# Connectors.net
KiCad netlist of a schematic drawn in Altium Designer
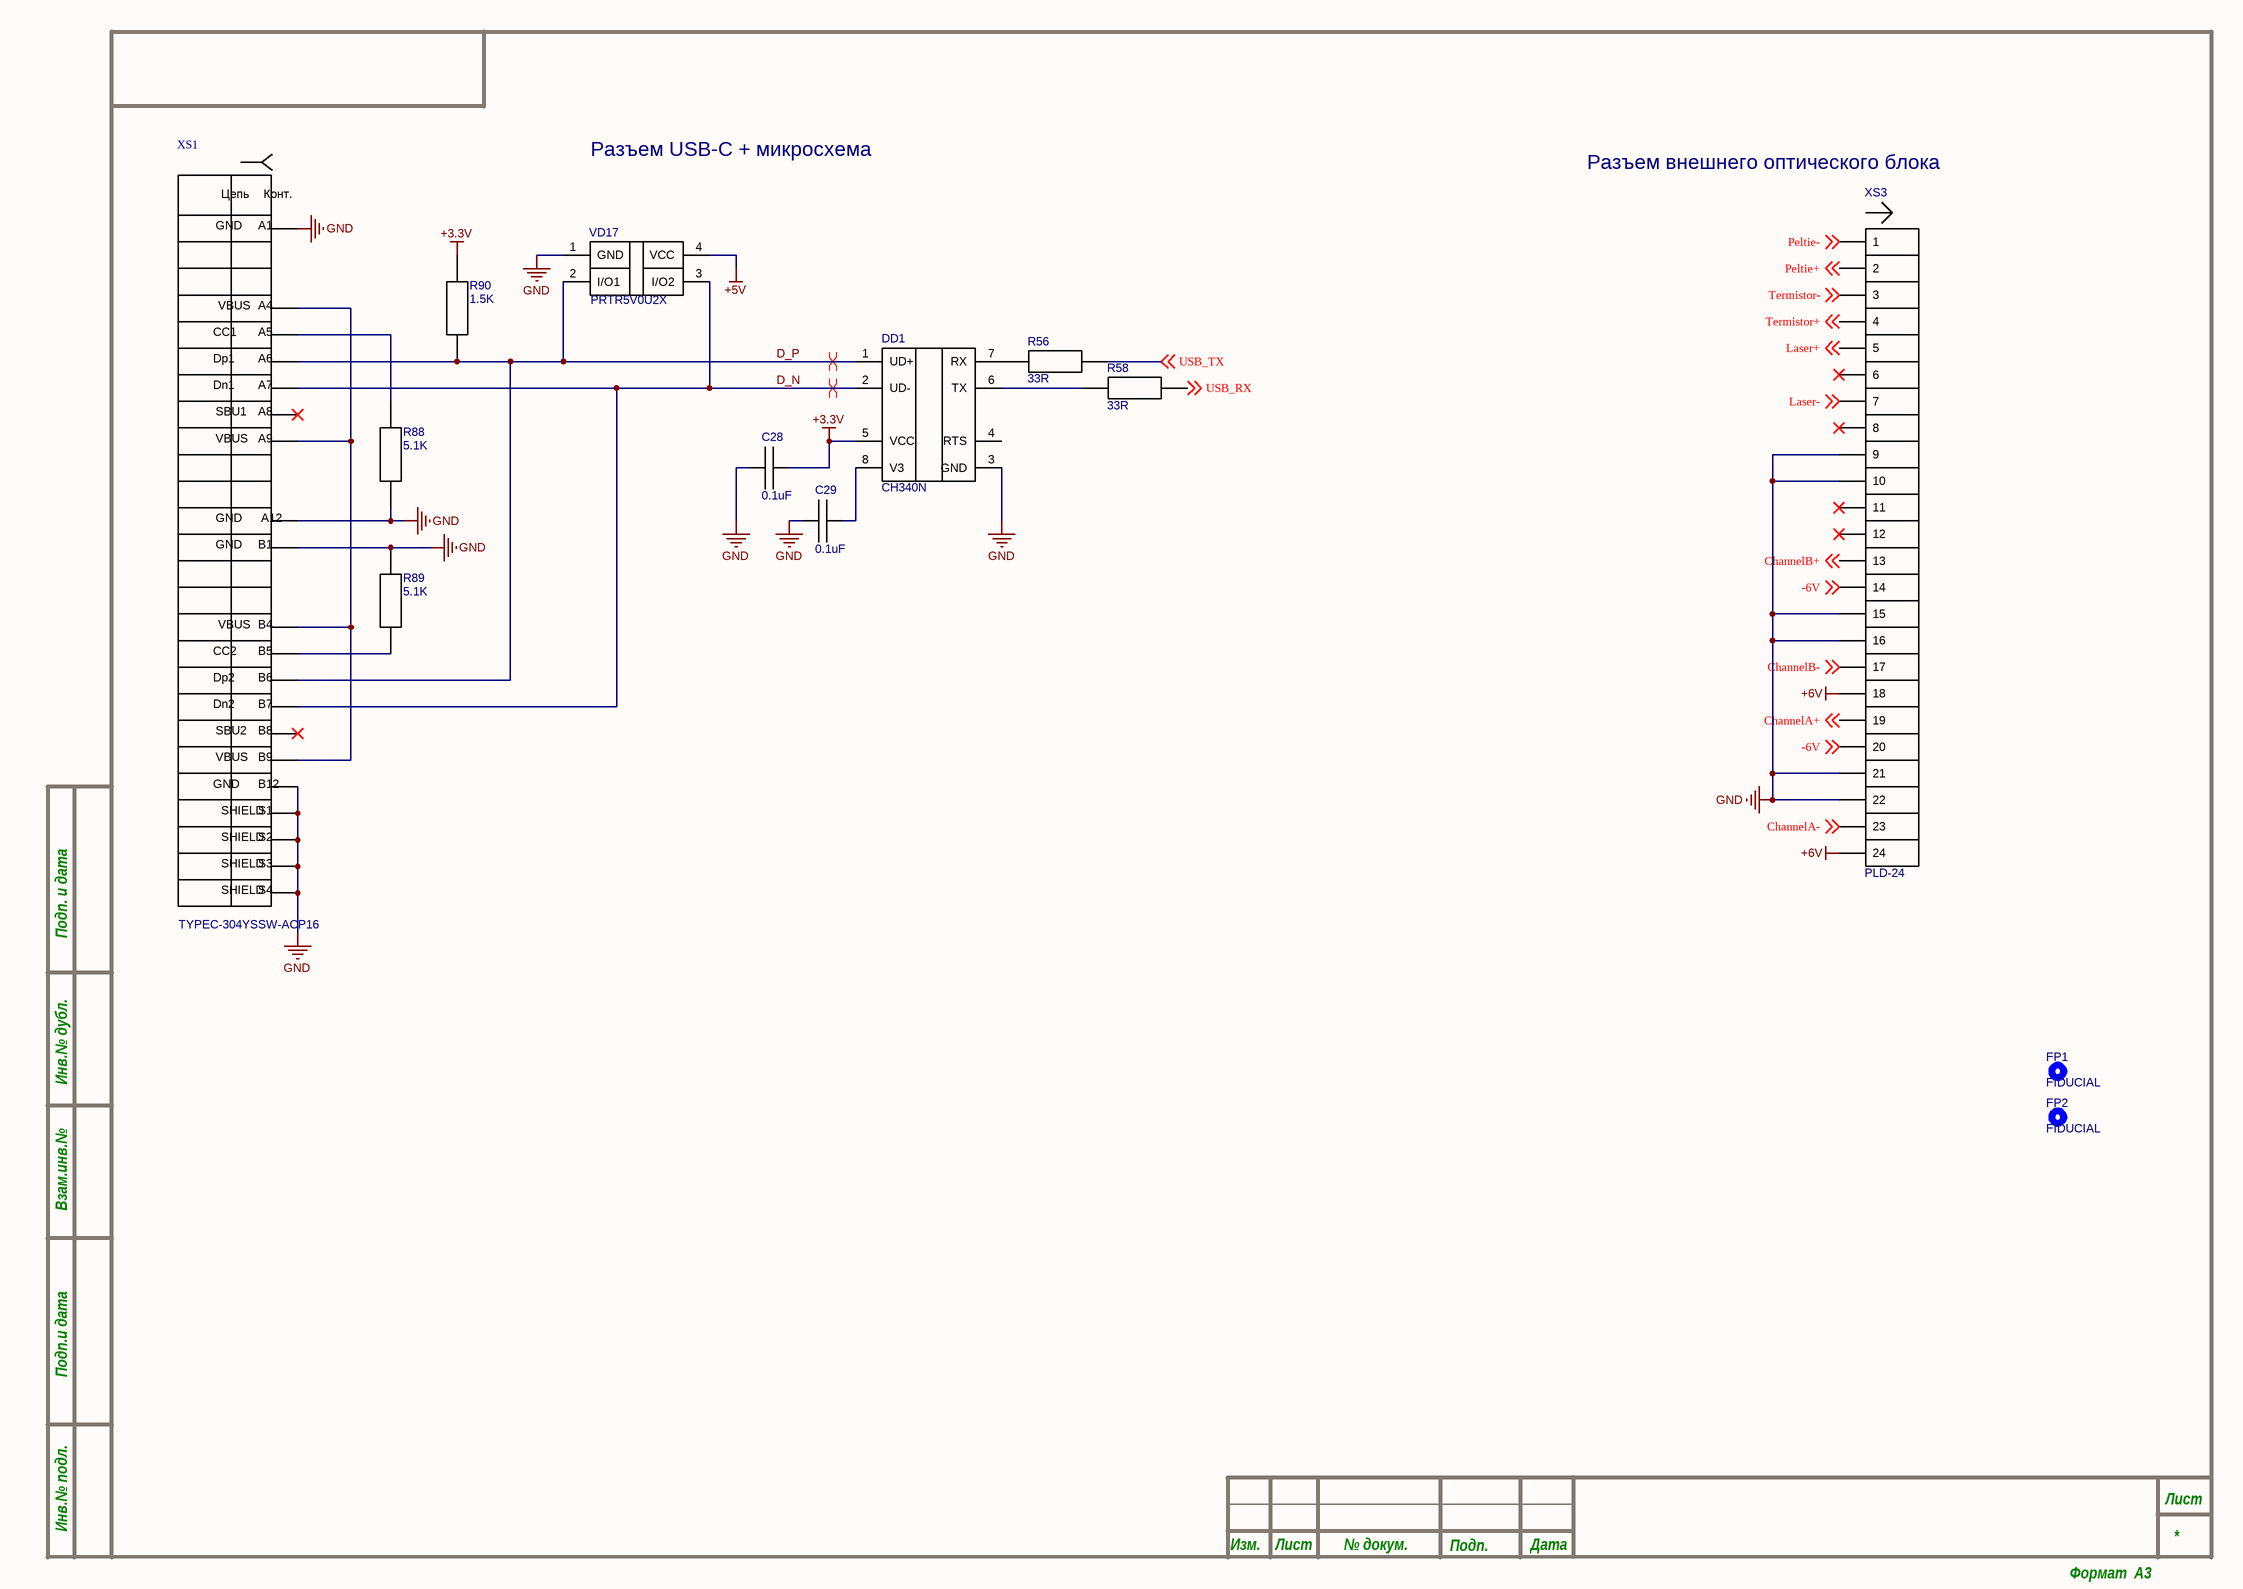
[diagram p0: Connectors.SchDoc]

(export (version "E")
  (design (tool "Eeschema 10.0.6"))
  (components
    (comp (ref "C28")
      (value "0.1uF")
      (footprint "0603C")
      (description "C0603 0.1UF 10% 50V")
      (fields
        (field (name "PART NUMBER") "SMD CAP CER 0.1UF ±10% 50V X7R 0603")
        (field (name "ADDED_BY") "anton@teslatec.ru")
      )
      (libsource (lib "Test_Stand_Pergam") (part "C0603-0.1UF 10% 50V"))
    )
    (comp (ref "C29")
      (value "0.1uF")
      (footprint "0603C")
      (description "C0603 0.1UF 10% 50V")
      (fields
        (field (name "PART NUMBER") "SMD CAP CER 0.1UF ±10% 50V X7R 0603")
        (field (name "ADDED_BY") "anton@teslatec.ru")
      )
      (libsource (lib "Test_Stand_Pergam") (part "C0603-0.1UF 10% 50V"))
    )
    (comp (ref "DD1")
      (value "CH340N")
      (footprint "SOP8")
      (description "USB to Serial Port Chip CH340, SOP-8")
      (fields (field (name "ADDED_BY") "irdolgopolowa@yandex.ru"))
      (libsource (lib "Test_Stand_Pergam") (part "CH340N"))
    )
    (comp (ref "FP1")
      (value "FIDUCIAL")
      (footprint "FIDICIAL POINT - R0.3")
      (fields (field (name "ADDER_BY") "ridel_av@teslatec.ru"))
      (libsource (lib "Test_Stand_Pergam") (part "FIDUCIAL_R0.3"))
    )
    (comp (ref "FP2")
      (value "FIDUCIAL")
      (footprint "FIDICIAL POINT - R0.3")
      (fields (field (name "ADDER_BY") "ridel_av@teslatec.ru"))
      (libsource (lib "Test_Stand_Pergam") (part "FIDUCIAL_R0.3"))
    )
    (comp (ref "R56")
      (value "33R")
      (footprint "R0402")
      (description "Resistor SMD 33R 1% 0402")
      (fields
        (field (name "PART NUMBER") "SMD RES 33R OHM 1% ±100ppm/°C 0402")
        (field (name "ADDED_BY") "Rutel@teslatec.ru")
      )
      (libsource (lib "Test_Stand_Pergam") (part "R0402-33R"))
    )
    (comp (ref "R58")
      (value "33R")
      (footprint "R0402")
      (description "Resistor SMD 33R 1% 0402")
      (fields
        (field (name "PART NUMBER") "SMD RES 33R OHM 1% ±100ppm/°C 0402")
        (field (name "ADDED_BY") "Rutel@teslatec.ru")
      )
      (libsource (lib "Test_Stand_Pergam") (part "R0402-33R"))
    )
    (comp (ref "R88")
      (value "5.1K")
      (footprint "R0402")
      (description "Resistor SMD 5.1K 1% 0402")
      (fields
        (field (name "PART NUMBER") "SMD RES 5.1 KOHM 1% ±100ppm/°C 0402")
        (field (name "ADDED_BY") "Rutel@teslatec.ru")
      )
      (libsource (lib "Test_Stand_Pergam") (part "R0402-5.1K"))
    )
    (comp (ref "R89")
      (value "5.1K")
      (footprint "R0402")
      (description "Resistor SMD 5.1K 1% 0402")
      (fields
        (field (name "PART NUMBER") "SMD RES 5.1 KOHM 1% ±100ppm/°C 0402")
        (field (name "ADDED_BY") "Rutel@teslatec.ru")
      )
      (libsource (lib "Test_Stand_Pergam") (part "R0402-5.1K"))
    )
    (comp (ref "R90")
      (value "1.5K")
      (footprint "R0402")
      (description "Resistor SMD 1.5K 1% 0402")
      (fields
        (field (name "PART NUMBER") "SMD RES 1.5 KOHM 1% ±100ppm/°C 0402")
        (field (name "ADDED_BY") "Rutel@teslatec.ru")
      )
      (libsource (lib "Test_Stand_Pergam") (part "R0402-1.5K"))
    )
    (comp (ref "VD17")
      (value "PRTR5V0U2X")
      (footprint "SOT143B")
      (description "PRTR5V0U2X, ESD(Rail-to-Rail), 1pF,  5V")
      (fields (field (name "ADDED_BY") "irdolgopolowa@yandex.ru"))
      (libsource (lib "Test_Stand_Pergam") (part "PRTR5V0U2X"))
    )
    (comp (ref "XS1")
      (value "TYPEC-304YSSW-ACP16")
      (footprint "USB-C 16P")
      (description "USB Type-C, 16 Pin")
      (fields (field (name "ADDED_BY") "ridel_av@teslatec.ru"))
      (libsource (lib "Test_Stand_Pergam") (part "TYPEC-304YSSW-ACP16"))
    )
    (comp (ref "XS3")
      (value "PLD-24")
      (footprint "PLD-24")
      (description "Pin Header Pitch 2.54mm")
      (fields (field (name "ADDED_BY") "andrew@teslatec.ru"))
      (libsource (lib "Test_Stand_Pergam") (part "PLD-24"))
    )
  )
  (nets
    (net (code "1") (name "+3.3V") (class "Default")
      (node (ref "C28") (pin "2") (pinfunction "2_2") (pintype "passive"))
      (node (ref "DD1") (pin "5") (pinfunction "VCC_5") (pintype "passive"))
      (node (ref "R90") (pin "2") (pinfunction "2_2") (pintype "passive"))
    )
    (net (code "2") (name "+5V") (class "Default")
      (node (ref "VD17") (pin "4") (pinfunction "VCC_4") (pintype "passive"))
    )
    (net (code "3") (name "+6V") (class "Default")
      (node (ref "XS3") (pin "18") (pinfunction "18_18") (pintype "passive"))
      (node (ref "XS3") (pin "24") (pinfunction "24_24") (pintype "passive"))
    )
    (net (code "4") (name "-6V") (class "Default")
      (node (ref "XS3") (pin "14") (pinfunction "14_14") (pintype "passive"))
      (node (ref "XS3") (pin "20") (pinfunction "20_20") (pintype "passive"))
    )
    (net (code "5") (name "/D_N") (class "Default")
      (node (ref "DD1") (pin "2") (pinfunction "UD-_2") (pintype "passive"))
      (node (ref "VD17") (pin "3") (pinfunction "I/O2_3") (pintype "passive"))
      (node (ref "XS1") (pin "A7") (pinfunction "Dn1_A7") (pintype "passive"))
      (node (ref "XS1") (pin "B7") (pinfunction "Dn2_B7") (pintype "passive"))
    )
    (net (code "6") (name "/D_P") (class "Default")
      (node (ref "DD1") (pin "1") (pinfunction "UD+_1") (pintype "passive"))
      (node (ref "R90") (pin "1") (pinfunction "1_1") (pintype "passive"))
      (node (ref "VD17") (pin "2") (pinfunction "I/O1_2") (pintype "passive"))
      (node (ref "XS1") (pin "A6") (pinfunction "Dp1_A6") (pintype "passive"))
      (node (ref "XS1") (pin "B6") (pinfunction "Dp2_B6") (pintype "passive"))
    )
    (net (code "7") (name "ChannelA+") (class "Default")
      (node (ref "XS3") (pin "19") (pinfunction "19_19") (pintype "passive"))
    )
    (net (code "8") (name "ChannelA-") (class "Default")
      (node (ref "XS3") (pin "23") (pinfunction "23_23") (pintype "passive"))
    )
    (net (code "9") (name "ChannelB+") (class "Default")
      (node (ref "XS3") (pin "13") (pinfunction "13_13") (pintype "passive"))
    )
    (net (code "10") (name "ChannelB-") (class "Default")
      (node (ref "XS3") (pin "17") (pinfunction "17_17") (pintype "passive"))
    )
    (net (code "11") (name "GND") (class "Default")
      (node (ref "C28") (pin "1") (pinfunction "1_1") (pintype "passive"))
      (node (ref "C29") (pin "1") (pinfunction "1_1") (pintype "passive"))
      (node (ref "DD1") (pin "3") (pinfunction "GND_3") (pintype "passive"))
      (node (ref "R88") (pin "1") (pinfunction "1_1") (pintype "passive"))
      (node (ref "R89") (pin "2") (pinfunction "2_2") (pintype "passive"))
      (node (ref "VD17") (pin "1") (pinfunction "GND_1") (pintype "passive"))
      (node (ref "XS1") (pin "A1/B12") (pinfunction "GND_A1/B12") (pintype "passive"))
      (node (ref "XS1") (pin "A12/B1") (pinfunction "GND_A12/B1") (pintype "passive"))
      (node (ref "XS1") (pin "S1") (pinfunction "SHIELD_S1") (pintype "passive"))
      (node (ref "XS1") (pin "S2") (pinfunction "SHIELD_S2") (pintype "passive"))
      (node (ref "XS1") (pin "S3") (pinfunction "SHIELD_S3") (pintype "passive"))
      (node (ref "XS1") (pin "S4") (pinfunction "SHIELD_S4") (pintype "passive"))
      (node (ref "XS3") (pin "10") (pinfunction "10_10") (pintype "passive"))
      (node (ref "XS3") (pin "15") (pinfunction "15_15") (pintype "passive"))
      (node (ref "XS3") (pin "16") (pinfunction "16_16") (pintype "passive"))
      (node (ref "XS3") (pin "21") (pinfunction "21_21") (pintype "passive"))
      (node (ref "XS3") (pin "22") (pinfunction "22_22") (pintype "passive"))
      (node (ref "XS3") (pin "9") (pinfunction "9_9") (pintype "passive"))
    )
    (net (code "12") (name "Laser+") (class "Default")
      (node (ref "XS3") (pin "5") (pinfunction "5_5") (pintype "passive"))
    )
    (net (code "13") (name "Laser-") (class "Default")
      (node (ref "XS3") (pin "7") (pinfunction "7_7") (pintype "passive"))
    )
    (net (code "14") (name "Net-(DD1-RX)") (class "Default")
      (node (ref "DD1") (pin "7") (pinfunction "RX_7") (pintype "passive"))
      (node (ref "R56") (pin "1") (pinfunction "1_1") (pintype "passive"))
    )
    (net (code "15") (name "Net-(DD1-TX)") (class "Default")
      (node (ref "DD1") (pin "6") (pinfunction "TX_6") (pintype "passive"))
      (node (ref "R58") (pin "1") (pinfunction "1_1") (pintype "passive"))
    )
    (net (code "16") (name "Net-(DD1-V3)") (class "Default")
      (node (ref "C29") (pin "2") (pinfunction "2_2") (pintype "passive"))
      (node (ref "DD1") (pin "8") (pinfunction "V3_8") (pintype "passive"))
    )
    (net (code "17") (name "Net-(XS1-CC1)") (class "Default")
      (node (ref "R88") (pin "2") (pinfunction "2_2") (pintype "passive"))
      (node (ref "XS1") (pin "A5") (pinfunction "CC1_A5") (pintype "passive"))
    )
    (net (code "18") (name "Net-(XS1-CC2)") (class "Default")
      (node (ref "R89") (pin "1") (pinfunction "1_1") (pintype "passive"))
      (node (ref "XS1") (pin "B5") (pinfunction "CC2_B5") (pintype "passive"))
    )
    (net (code "19") (name "Net-(XS1-VBUS-PadA4{slash}B9)") (class "Default")
      (node (ref "XS1") (pin "A4/B9") (pinfunction "VBUS_A4/B9") (pintype "passive"))
      (node (ref "XS1") (pin "A9/B4") (pinfunction "VBUS_A9/B4") (pintype "passive"))
    )
    (net (code "20") (name "Peltie+") (class "Default")
      (node (ref "XS3") (pin "2") (pinfunction "2_2") (pintype "passive"))
    )
    (net (code "21") (name "Peltie-") (class "Default")
      (node (ref "XS3") (pin "1") (pinfunction "1_1") (pintype "passive"))
    )
    (net (code "22") (name "Termistor+") (class "Default")
      (node (ref "XS3") (pin "4") (pinfunction "4_4") (pintype "passive"))
    )
    (net (code "23") (name "Termistor-") (class "Default")
      (node (ref "XS3") (pin "3") (pinfunction "3_3") (pintype "passive"))
    )
    (net (code "24") (name "USB_RX") (class "Default")
      (node (ref "R58") (pin "2") (pinfunction "2_2") (pintype "passive"))
    )
    (net (code "25") (name "USB_TX") (class "Default")
      (node (ref "R56") (pin "2") (pinfunction "2_2") (pintype "passive"))
    )
    (net (code "26") (name "unconnected-(DD1-RTS-Pad4)") (class "Default")
      (node (ref "DD1") (pin "4") (pinfunction "RTS_4") (pintype "passive"))
    )
    (net (code "27") (name "unconnected-(XS1-SBU1-PadA8)") (class "Default")
      (node (ref "XS1") (pin "A8") (pinfunction "SBU1_A8") (pintype "passive+no_connect"))
    )
    (net (code "28") (name "unconnected-(XS1-SBU2-PadB8)") (class "Default")
      (node (ref "XS1") (pin "B8") (pinfunction "SBU2_B8") (pintype "passive+no_connect"))
    )
    (net (code "29") (name "unconnected-(XS3-Pad6)") (class "Default")
      (node (ref "XS3") (pin "6") (pinfunction "6_6") (pintype "passive+no_connect"))
    )
    (net (code "30") (name "unconnected-(XS3-Pad8)") (class "Default")
      (node (ref "XS3") (pin "8") (pinfunction "8_8") (pintype "passive+no_connect"))
    )
    (net (code "31") (name "unconnected-(XS3-Pad11)") (class "Default")
      (node (ref "XS3") (pin "11") (pinfunction "11_11") (pintype "passive+no_connect"))
    )
    (net (code "32") (name "unconnected-(XS3-Pad12)") (class "Default")
      (node (ref "XS3") (pin "12") (pinfunction "12_12") (pintype "passive+no_connect"))
    )
  )
)
